# Digital_Port_A_Button.net
KiCad netlist of a schematic drawn in Altium Designer
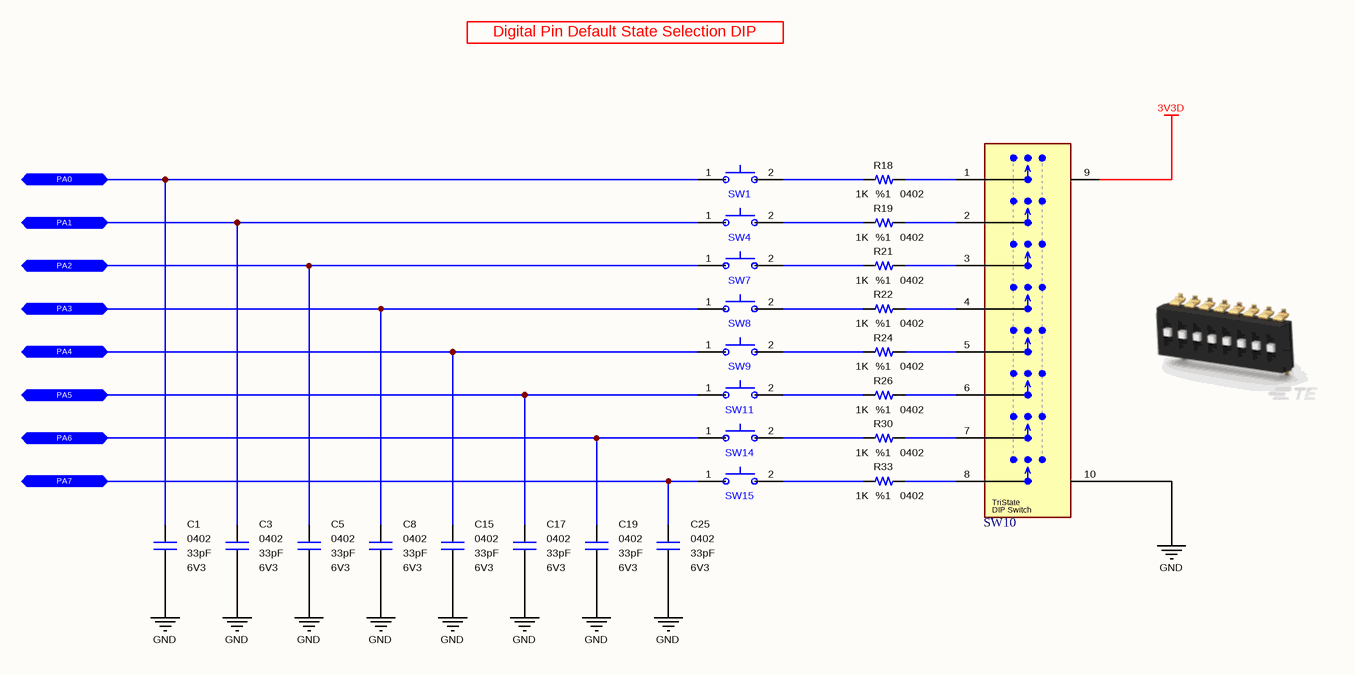
[diagram p0: Digital Port A Button.SchDoc]

(export (version "E")
  (design (tool "Eeschema 10.0.6"))
  (components
    (comp (ref "C1")
      (value "33pF")
      (footprint "CAPACITOR_0402")
      (description "Capacitor - 33pF [0402] (Ceramic)")
      (fields
        (field (name "MANUFACTURER PART NUMBER") "C0402C330J9RACAUTO")
        (field (name "MOUSER PART NUMBER") "80-C0402C330J9RAUTO")
        (field (name "CASE") "0402")
        (field (name "VOLTAGE") "6V3")
      )
      (libsource (lib "Ovoo_Library") (part "Capacitor - 33pF [0402-6V3]"))
    )
    (comp (ref "C3")
      (value "33pF")
      (footprint "CAPACITOR_0402")
      (description "Capacitor - 33pF [0402] (Ceramic)")
      (fields
        (field (name "MANUFACTURER PART NUMBER") "C0402C330J9RACAUTO")
        (field (name "MOUSER PART NUMBER") "80-C0402C330J9RAUTO")
        (field (name "CASE") "0402")
        (field (name "VOLTAGE") "6V3")
      )
      (libsource (lib "Ovoo_Library") (part "Capacitor - 33pF [0402-6V3]"))
    )
    (comp (ref "C5")
      (value "33pF")
      (footprint "CAPACITOR_0402")
      (description "Capacitor - 33pF [0402] (Ceramic)")
      (fields
        (field (name "MANUFACTURER PART NUMBER") "C0402C330J9RACAUTO")
        (field (name "MOUSER PART NUMBER") "80-C0402C330J9RAUTO")
        (field (name "CASE") "0402")
        (field (name "VOLTAGE") "6V3")
      )
      (libsource (lib "Ovoo_Library") (part "Capacitor - 33pF [0402-6V3]"))
    )
    (comp (ref "C8")
      (value "33pF")
      (footprint "CAPACITOR_0402")
      (description "Capacitor - 33pF [0402] (Ceramic)")
      (fields
        (field (name "MANUFACTURER PART NUMBER") "C0402C330J9RACAUTO")
        (field (name "MOUSER PART NUMBER") "80-C0402C330J9RAUTO")
        (field (name "CASE") "0402")
        (field (name "VOLTAGE") "6V3")
      )
      (libsource (lib "Ovoo_Library") (part "Capacitor - 33pF [0402-6V3]"))
    )
    (comp (ref "C15")
      (value "33pF")
      (footprint "CAPACITOR_0402")
      (description "Capacitor - 33pF [0402] (Ceramic)")
      (fields
        (field (name "MANUFACTURER PART NUMBER") "C0402C330J9RACAUTO")
        (field (name "MOUSER PART NUMBER") "80-C0402C330J9RAUTO")
        (field (name "CASE") "0402")
        (field (name "VOLTAGE") "6V3")
      )
      (libsource (lib "Ovoo_Library") (part "Capacitor - 33pF [0402-6V3]"))
    )
    (comp (ref "C17")
      (value "33pF")
      (footprint "CAPACITOR_0402")
      (description "Capacitor - 33pF [0402] (Ceramic)")
      (fields
        (field (name "MANUFACTURER PART NUMBER") "C0402C330J9RACAUTO")
        (field (name "MOUSER PART NUMBER") "80-C0402C330J9RAUTO")
        (field (name "CASE") "0402")
        (field (name "VOLTAGE") "6V3")
      )
      (libsource (lib "Ovoo_Library") (part "Capacitor - 33pF [0402-6V3]"))
    )
    (comp (ref "C19")
      (value "33pF")
      (footprint "CAPACITOR_0402")
      (description "Capacitor - 33pF [0402] (Ceramic)")
      (fields
        (field (name "MANUFACTURER PART NUMBER") "C0402C330J9RACAUTO")
        (field (name "MOUSER PART NUMBER") "80-C0402C330J9RAUTO")
        (field (name "CASE") "0402")
        (field (name "VOLTAGE") "6V3")
      )
      (libsource (lib "Ovoo_Library") (part "Capacitor - 33pF [0402-6V3]"))
    )
    (comp (ref "C25")
      (value "33pF")
      (footprint "CAPACITOR_0402")
      (description "Capacitor - 33pF [0402] (Ceramic)")
      (fields
        (field (name "MANUFACTURER PART NUMBER") "C0402C330J9RACAUTO")
        (field (name "MOUSER PART NUMBER") "80-C0402C330J9RAUTO")
        (field (name "CASE") "0402")
        (field (name "VOLTAGE") "6V3")
      )
      (libsource (lib "Ovoo_Library") (part "Capacitor - 33pF [0402-6V3]"))
    )
    (comp (ref "R18")
      (value "1K")
      (footprint "RESISTOR_0402")
      (description "Thick Film Resistors - SMD 1/16 W 1.0 Kohms 1%")
      (fields
        (field (name "MANUFACTURER PART NUMBER") "CRCW04021K00FKED")
        (field (name "MOUSER PART NUMBER") "71-CRCW0402-1.0K-E3")
        (field (name "TOLERANCE") "%1")
        (field (name "CASE") "0402")
      )
      (libsource (lib "Ovoo_Library") (part "Resistor - 1K"))
    )
    (comp (ref "R19")
      (value "1K")
      (footprint "RESISTOR_0402")
      (description "Thick Film Resistors - SMD 1/16 W 1.0 Kohms 1%")
      (fields
        (field (name "MANUFACTURER PART NUMBER") "CRCW04021K00FKED")
        (field (name "MOUSER PART NUMBER") "71-CRCW0402-1.0K-E3")
        (field (name "TOLERANCE") "%1")
        (field (name "CASE") "0402")
      )
      (libsource (lib "Ovoo_Library") (part "Resistor - 1K"))
    )
    (comp (ref "R21")
      (value "1K")
      (footprint "RESISTOR_0402")
      (description "Thick Film Resistors - SMD 1/16 W 1.0 Kohms 1%")
      (fields
        (field (name "MANUFACTURER PART NUMBER") "CRCW04021K00FKED")
        (field (name "MOUSER PART NUMBER") "71-CRCW0402-1.0K-E3")
        (field (name "TOLERANCE") "%1")
        (field (name "CASE") "0402")
      )
      (libsource (lib "Ovoo_Library") (part "Resistor - 1K"))
    )
    (comp (ref "R22")
      (value "1K")
      (footprint "RESISTOR_0402")
      (description "Thick Film Resistors - SMD 1/16 W 1.0 Kohms 1%")
      (fields
        (field (name "MANUFACTURER PART NUMBER") "CRCW04021K00FKED")
        (field (name "MOUSER PART NUMBER") "71-CRCW0402-1.0K-E3")
        (field (name "TOLERANCE") "%1")
        (field (name "CASE") "0402")
      )
      (libsource (lib "Ovoo_Library") (part "Resistor - 1K"))
    )
    (comp (ref "R24")
      (value "1K")
      (footprint "RESISTOR_0402")
      (description "Thick Film Resistors - SMD 1/16 W 1.0 Kohms 1%")
      (fields
        (field (name "MANUFACTURER PART NUMBER") "CRCW04021K00FKED")
        (field (name "MOUSER PART NUMBER") "71-CRCW0402-1.0K-E3")
        (field (name "TOLERANCE") "%1")
        (field (name "CASE") "0402")
      )
      (libsource (lib "Ovoo_Library") (part "Resistor - 1K"))
    )
    (comp (ref "R26")
      (value "1K")
      (footprint "RESISTOR_0402")
      (description "Thick Film Resistors - SMD 1/16 W 1.0 Kohms 1%")
      (fields
        (field (name "MANUFACTURER PART NUMBER") "CRCW04021K00FKED")
        (field (name "MOUSER PART NUMBER") "71-CRCW0402-1.0K-E3")
        (field (name "TOLERANCE") "%1")
        (field (name "CASE") "0402")
      )
      (libsource (lib "Ovoo_Library") (part "Resistor - 1K"))
    )
    (comp (ref "R30")
      (value "1K")
      (footprint "RESISTOR_0402")
      (description "Thick Film Resistors - SMD 1/16 W 1.0 Kohms 1%")
      (fields
        (field (name "MANUFACTURER PART NUMBER") "CRCW04021K00FKED")
        (field (name "MOUSER PART NUMBER") "71-CRCW0402-1.0K-E3")
        (field (name "TOLERANCE") "%1")
        (field (name "CASE") "0402")
      )
      (libsource (lib "Ovoo_Library") (part "Resistor - 1K"))
    )
    (comp (ref "R33")
      (value "1K")
      (footprint "RESISTOR_0402")
      (description "Thick Film Resistors - SMD 1/16 W 1.0 Kohms 1%")
      (fields
        (field (name "MANUFACTURER PART NUMBER") "CRCW04021K00FKED")
        (field (name "MOUSER PART NUMBER") "71-CRCW0402-1.0K-E3")
        (field (name "TOLERANCE") "%1")
        (field (name "CASE") "0402")
      )
      (libsource (lib "Ovoo_Library") (part "Resistor - 1K"))
    )
    (comp (ref "SW1")
      (value "Tactile Switches")
      (footprint "PTS526_Switch")
      (description "Tactile Switches 50mA 12VDC, 5.2x5.2mm, 0.8mm H, 260gf, G leads.")
      (fields
        (field (name "MANUFACTURER PART NUMBER") "PTS526 SK08 SMTR2 LFS")
        (field (name "MOUSER PART NUMBER") "611-PTS526SK08SMTR2L")
      )
      (libsource (lib "Ovoo_Library") (part "Switch - Tactile"))
    )
    (comp (ref "SW4")
      (value "Tactile Switches")
      (footprint "PTS526_Switch")
      (description "Tactile Switches 50mA 12VDC, 5.2x5.2mm, 0.8mm H, 260gf, G leads.")
      (fields
        (field (name "MANUFACTURER PART NUMBER") "PTS526 SK08 SMTR2 LFS")
        (field (name "MOUSER PART NUMBER") "611-PTS526SK08SMTR2L")
      )
      (libsource (lib "Ovoo_Library") (part "Switch - Tactile"))
    )
    (comp (ref "SW7")
      (value "Tactile Switches")
      (footprint "PTS526_Switch")
      (description "Tactile Switches 50mA 12VDC, 5.2x5.2mm, 0.8mm H, 260gf, G leads.")
      (fields
        (field (name "MANUFACTURER PART NUMBER") "PTS526 SK08 SMTR2 LFS")
        (field (name "MOUSER PART NUMBER") "611-PTS526SK08SMTR2L")
      )
      (libsource (lib "Ovoo_Library") (part "Switch - Tactile"))
    )
    (comp (ref "SW8")
      (value "Tactile Switches")
      (footprint "PTS526_Switch")
      (description "Tactile Switches 50mA 12VDC, 5.2x5.2mm, 0.8mm H, 260gf, G leads.")
      (fields
        (field (name "MANUFACTURER PART NUMBER") "PTS526 SK08 SMTR2 LFS")
        (field (name "MOUSER PART NUMBER") "611-PTS526SK08SMTR2L")
      )
      (libsource (lib "Ovoo_Library") (part "Switch - Tactile"))
    )
    (comp (ref "SW9")
      (value "Tactile Switches")
      (footprint "PTS526_Switch")
      (description "Tactile Switches 50mA 12VDC, 5.2x5.2mm, 0.8mm H, 260gf, G leads.")
      (fields
        (field (name "MANUFACTURER PART NUMBER") "PTS526 SK08 SMTR2 LFS")
        (field (name "MOUSER PART NUMBER") "611-PTS526SK08SMTR2L")
      )
      (libsource (lib "Ovoo_Library") (part "Switch - Tactile"))
    )
    (comp (ref "SW10")
      (value "DIP Switches/SIP Switches")
      (footprint "TDS08SGNNTR04")
      (description "DIP Switches/SIP Switches TRI-STATE DIP 8P G RAISED T&R")
      (fields
        (field (name "MANUFACTURER PART NUMBER") "TDS08SGNNTR04")
        (field (name "MOUSER PART NUMBER") "506-TDS08SGNNTR04")
      )
      (libsource (lib "Ovoo_Library") (part "Switch - DIP Switch (8 Pole TriState)"))
    )
    (comp (ref "SW11")
      (value "Tactile Switches")
      (footprint "PTS526_Switch")
      (description "Tactile Switches 50mA 12VDC, 5.2x5.2mm, 0.8mm H, 260gf, G leads.")
      (fields
        (field (name "MANUFACTURER PART NUMBER") "PTS526 SK08 SMTR2 LFS")
        (field (name "MOUSER PART NUMBER") "611-PTS526SK08SMTR2L")
      )
      (libsource (lib "Ovoo_Library") (part "Switch - Tactile"))
    )
    (comp (ref "SW14")
      (value "Tactile Switches")
      (footprint "PTS526_Switch")
      (description "Tactile Switches 50mA 12VDC, 5.2x5.2mm, 0.8mm H, 260gf, G leads.")
      (fields
        (field (name "MANUFACTURER PART NUMBER") "PTS526 SK08 SMTR2 LFS")
        (field (name "MOUSER PART NUMBER") "611-PTS526SK08SMTR2L")
      )
      (libsource (lib "Ovoo_Library") (part "Switch - Tactile"))
    )
    (comp (ref "SW15")
      (value "Tactile Switches")
      (footprint "PTS526_Switch")
      (description "Tactile Switches 50mA 12VDC, 5.2x5.2mm, 0.8mm H, 260gf, G leads.")
      (fields
        (field (name "MANUFACTURER PART NUMBER") "PTS526 SK08 SMTR2 LFS")
        (field (name "MOUSER PART NUMBER") "611-PTS526SK08SMTR2L")
      )
      (libsource (lib "Ovoo_Library") (part "Switch - Tactile"))
    )
  )
  (nets
    (net (code "1") (name "/PA0") (class "Default")
      (node (ref "C1") (pin "2") (pinfunction "2_2") (pintype "passive"))
      (node (ref "SW1") (pin "1") (pinfunction "NC_1") (pintype "passive"))
    )
    (net (code "2") (name "/PA1") (class "Default")
      (node (ref "C3") (pin "2") (pinfunction "2_2") (pintype "passive"))
      (node (ref "SW4") (pin "1") (pinfunction "NC_1") (pintype "passive"))
    )
    (net (code "3") (name "/PA2") (class "Default")
      (node (ref "C5") (pin "2") (pinfunction "2_2") (pintype "passive"))
      (node (ref "SW7") (pin "1") (pinfunction "NC_1") (pintype "passive"))
    )
    (net (code "4") (name "/PA3") (class "Default")
      (node (ref "C8") (pin "2") (pinfunction "2_2") (pintype "passive"))
      (node (ref "SW8") (pin "1") (pinfunction "NC_1") (pintype "passive"))
    )
    (net (code "5") (name "/PA4") (class "Default")
      (node (ref "C15") (pin "2") (pinfunction "2_2") (pintype "passive"))
      (node (ref "SW9") (pin "1") (pinfunction "NC_1") (pintype "passive"))
    )
    (net (code "6") (name "/PA5") (class "Default")
      (node (ref "C17") (pin "2") (pinfunction "2_2") (pintype "passive"))
      (node (ref "SW11") (pin "1") (pinfunction "NC_1") (pintype "passive"))
    )
    (net (code "7") (name "/PA6") (class "Default")
      (node (ref "C19") (pin "2") (pinfunction "2_2") (pintype "passive"))
      (node (ref "SW14") (pin "1") (pinfunction "NC_1") (pintype "passive"))
    )
    (net (code "8") (name "/PA7") (class "Default")
      (node (ref "C25") (pin "2") (pinfunction "2_2") (pintype "passive"))
      (node (ref "SW15") (pin "1") (pinfunction "NC_1") (pintype "passive"))
    )
    (net (code "9") (name "3V3D") (class "Default")
      (node (ref "SW10") (pin "9") (pinfunction "VCC_9") (pintype "passive"))
    )
    (net (code "10") (name "GND") (class "Default")
      (node (ref "C1") (pin "1") (pinfunction "1_1") (pintype "passive"))
      (node (ref "C15") (pin "1") (pinfunction "1_1") (pintype "passive"))
      (node (ref "C17") (pin "1") (pinfunction "1_1") (pintype "passive"))
      (node (ref "C19") (pin "1") (pinfunction "1_1") (pintype "passive"))
      (node (ref "C25") (pin "1") (pinfunction "1_1") (pintype "passive"))
      (node (ref "C3") (pin "1") (pinfunction "1_1") (pintype "passive"))
      (node (ref "C5") (pin "1") (pinfunction "1_1") (pintype "passive"))
      (node (ref "C8") (pin "1") (pinfunction "1_1") (pintype "passive"))
      (node (ref "SW10") (pin "10") (pinfunction "GND_10") (pintype "passive"))
    )
    (net (code "11") (name "Net-(R18-Pad1)") (class "Default")
      (node (ref "R18") (pin "1") (pinfunction "1_1") (pintype "passive"))
      (node (ref "SW10") (pin "1") (pinfunction "1_1") (pintype "passive"))
    )
    (net (code "12") (name "Net-(R19-Pad1)") (class "Default")
      (node (ref "R19") (pin "1") (pinfunction "1_1") (pintype "passive"))
      (node (ref "SW10") (pin "2") (pinfunction "2_2") (pintype "passive"))
    )
    (net (code "13") (name "Net-(R21-Pad1)") (class "Default")
      (node (ref "R21") (pin "1") (pinfunction "1_1") (pintype "passive"))
      (node (ref "SW10") (pin "3") (pinfunction "3_3") (pintype "passive"))
    )
    (net (code "14") (name "Net-(R22-Pad1)") (class "Default")
      (node (ref "R22") (pin "1") (pinfunction "1_1") (pintype "passive"))
      (node (ref "SW10") (pin "4") (pinfunction "4_4") (pintype "passive"))
    )
    (net (code "15") (name "Net-(R24-Pad1)") (class "Default")
      (node (ref "R24") (pin "1") (pinfunction "1_1") (pintype "passive"))
      (node (ref "SW10") (pin "5") (pinfunction "5_5") (pintype "passive"))
    )
    (net (code "16") (name "Net-(R26-Pad1)") (class "Default")
      (node (ref "R26") (pin "1") (pinfunction "1_1") (pintype "passive"))
      (node (ref "SW10") (pin "6") (pinfunction "6_6") (pintype "passive"))
    )
    (net (code "17") (name "Net-(R30-Pad1)") (class "Default")
      (node (ref "R30") (pin "1") (pinfunction "1_1") (pintype "passive"))
      (node (ref "SW10") (pin "7") (pinfunction "7_7") (pintype "passive"))
    )
    (net (code "18") (name "Net-(R33-Pad1)") (class "Default")
      (node (ref "R33") (pin "1") (pinfunction "1_1") (pintype "passive"))
      (node (ref "SW10") (pin "8") (pinfunction "8_8") (pintype "passive"))
    )
    (net (code "19") (name "Net-(SW1-COM)") (class "Default")
      (node (ref "R18") (pin "2") (pinfunction "2_2") (pintype "passive"))
      (node (ref "SW1") (pin "2") (pinfunction "COM_2") (pintype "passive"))
    )
    (net (code "20") (name "Net-(SW4-COM)") (class "Default")
      (node (ref "R19") (pin "2") (pinfunction "2_2") (pintype "passive"))
      (node (ref "SW4") (pin "2") (pinfunction "COM_2") (pintype "passive"))
    )
    (net (code "21") (name "Net-(SW7-COM)") (class "Default")
      (node (ref "R21") (pin "2") (pinfunction "2_2") (pintype "passive"))
      (node (ref "SW7") (pin "2") (pinfunction "COM_2") (pintype "passive"))
    )
    (net (code "22") (name "Net-(SW8-COM)") (class "Default")
      (node (ref "R22") (pin "2") (pinfunction "2_2") (pintype "passive"))
      (node (ref "SW8") (pin "2") (pinfunction "COM_2") (pintype "passive"))
    )
    (net (code "23") (name "Net-(SW9-COM)") (class "Default")
      (node (ref "R24") (pin "2") (pinfunction "2_2") (pintype "passive"))
      (node (ref "SW9") (pin "2") (pinfunction "COM_2") (pintype "passive"))
    )
    (net (code "24") (name "Net-(SW11-COM)") (class "Default")
      (node (ref "R26") (pin "2") (pinfunction "2_2") (pintype "passive"))
      (node (ref "SW11") (pin "2") (pinfunction "COM_2") (pintype "passive"))
    )
    (net (code "25") (name "Net-(SW14-COM)") (class "Default")
      (node (ref "R30") (pin "2") (pinfunction "2_2") (pintype "passive"))
      (node (ref "SW14") (pin "2") (pinfunction "COM_2") (pintype "passive"))
    )
    (net (code "26") (name "Net-(SW15-COM)") (class "Default")
      (node (ref "R33") (pin "2") (pinfunction "2_2") (pintype "passive"))
      (node (ref "SW15") (pin "2") (pinfunction "COM_2") (pintype "passive"))
    )
  )
)
